# MotorCell_noPow.net
KiCad netlist of a schematic drawn in Altium Designer
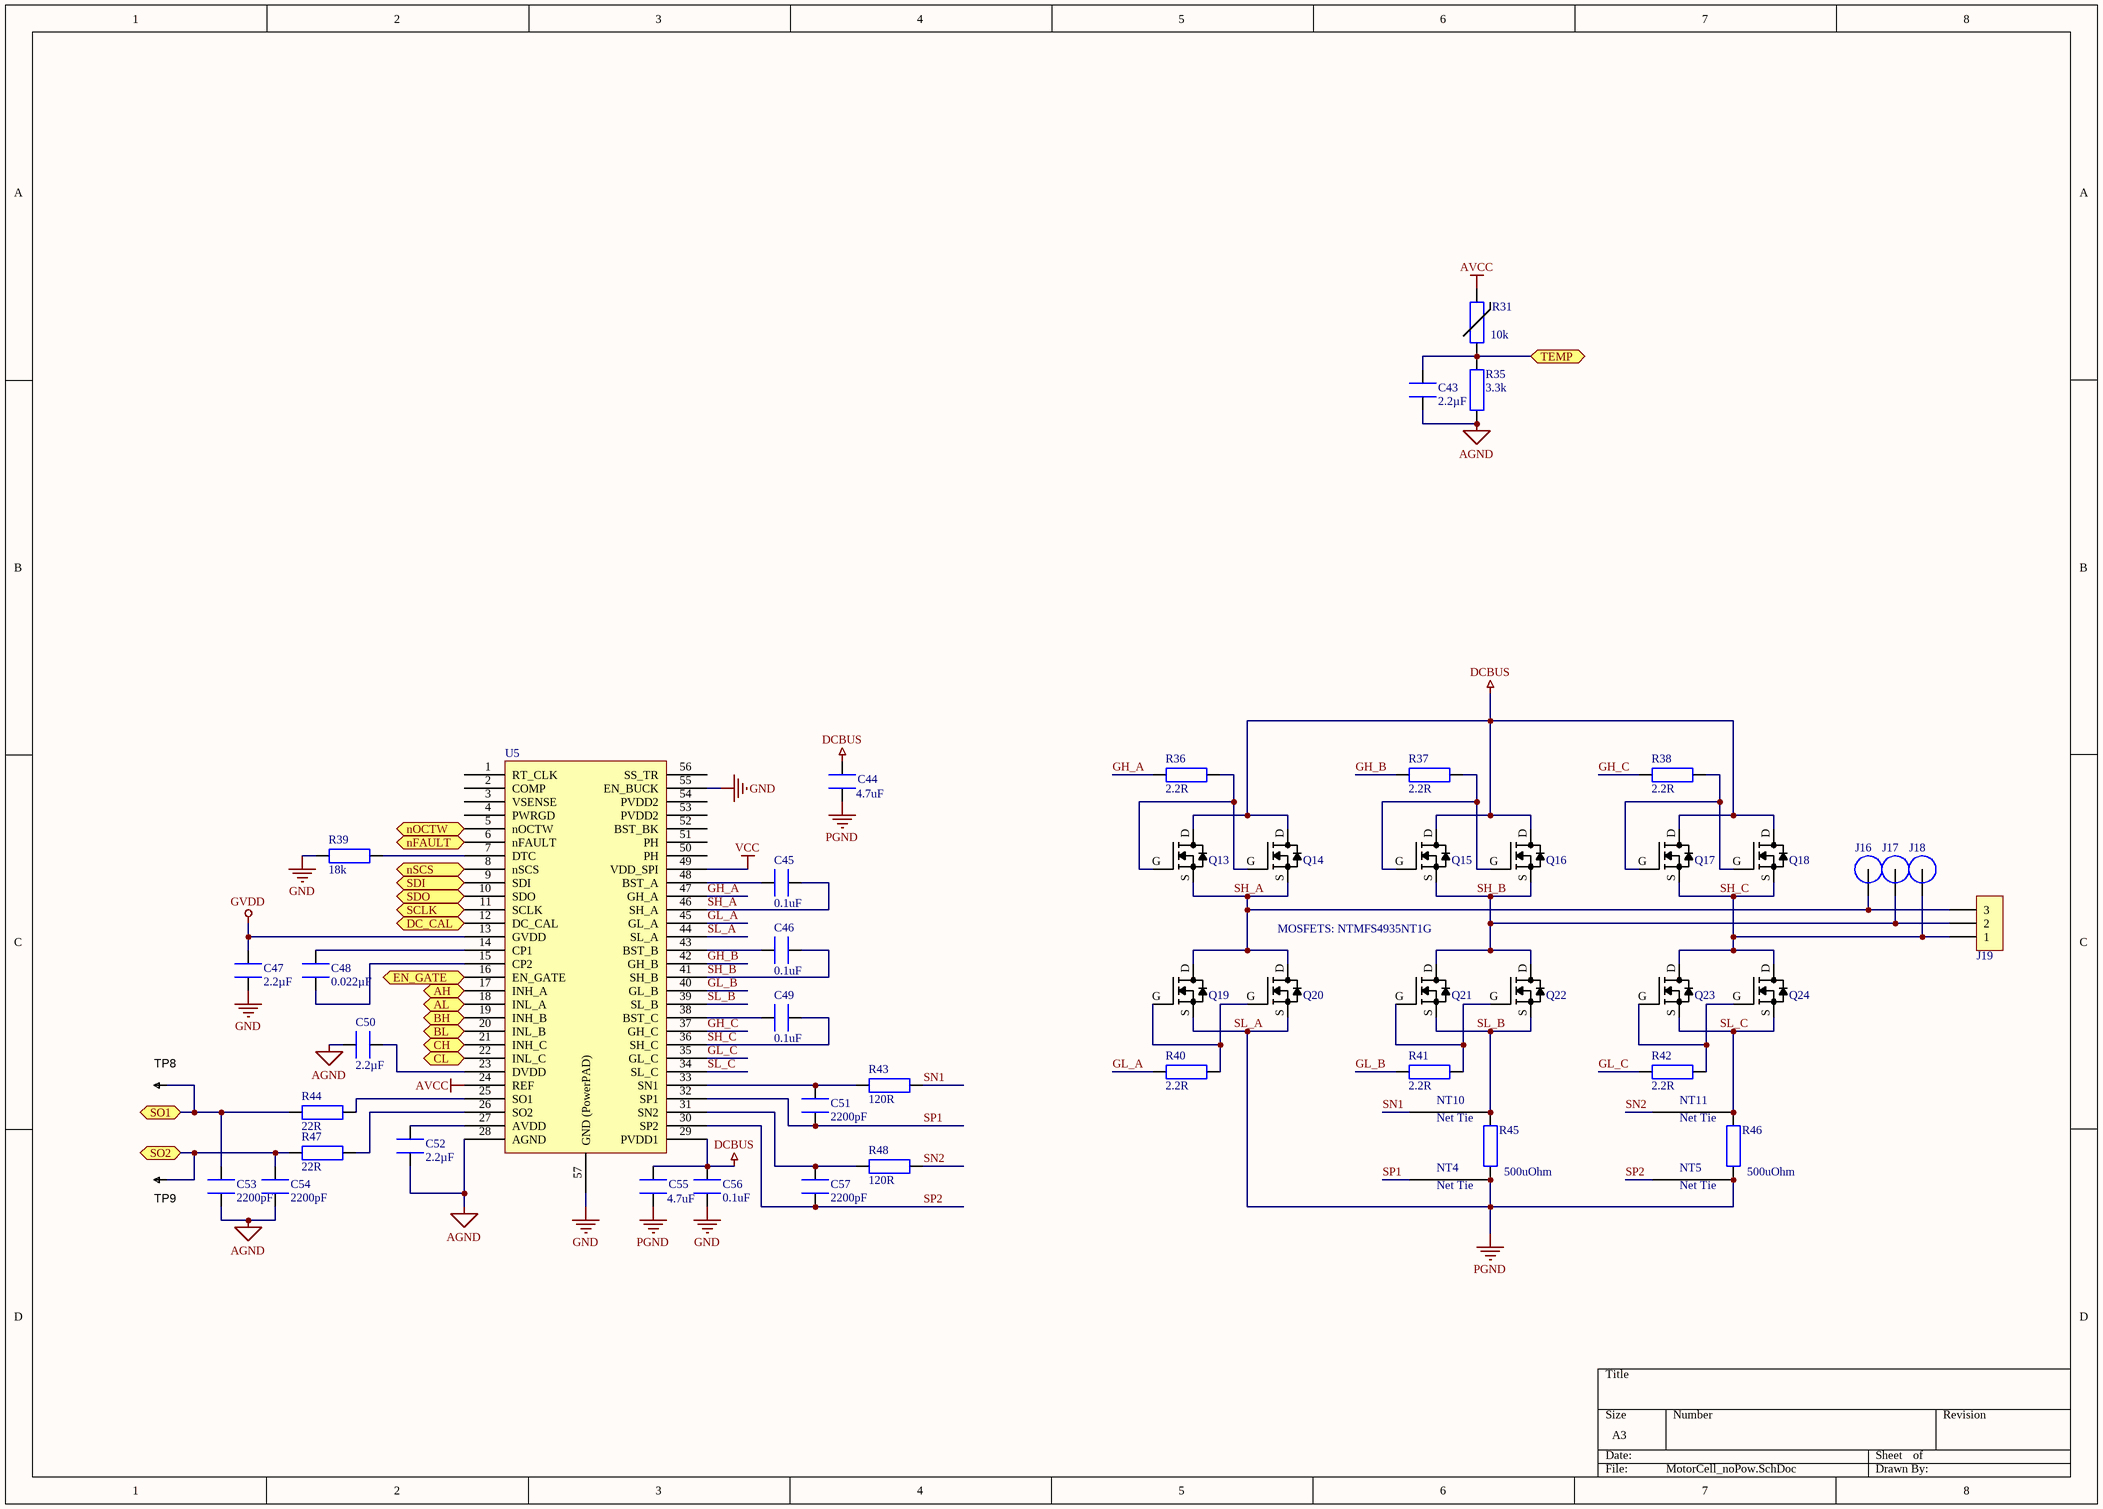
[diagram p0: MotorCell_noPow.SchDoc]

(export (version "E")
  (design (tool "Eeschema 10.0.6"))
  (components
    (comp (ref "C43")
      (value "2.2µF")
      (footprint "CAPC1608X09L")
      (description "CAP CER 2.2UF 16V X5R 0603")
      (fields
        (field (name "MANUFACTURER") "Murata Electronics North America")
        (field (name "MANUFACTURER PART NUMBER") "GRM188R61C225KE15D")
      )
      (libsource (lib "CustomComponents") (part "GRM188R61C225KE15D"))
    )
    (comp (ref "C44")
      (value "4.7uF")
      (footprint "CAPC2012X09N")
      (description "CAP CER 4.7UF 35V X5R 0805")
      (fields
        (field (name "MANUFACTURER") "Murata Electronics North America")
        (field (name "TOLERANCE") "±10%")
      )
      (libsource (lib "CustomComponents") (part "GRM219R6YA475KA73D"))
    )
    (comp (ref "C45")
      (value "0.1uF")
      (footprint "CAPC1608X09L")
      (description "CAP CER 0.1UF 50V X7R 0603")
      (fields
        (field (name "MANUFACTURER") "Murata Electronics North America")
        (field (name "MANUFACTURER PART NUMBER") "GRM188R71H104KA93D")
      )
      (libsource (lib "CustomComponents") (part "GRM188R71H104KA93D"))
    )
    (comp (ref "C46")
      (value "0.1uF")
      (footprint "CAPC1608X09L")
      (description "CAP CER 0.1UF 50V X7R 0603")
      (fields
        (field (name "MANUFACTURER") "Murata Electronics North America")
        (field (name "MANUFACTURER PART NUMBER") "GRM188R71H104KA93D")
      )
      (libsource (lib "CustomComponents") (part "GRM188R71H104KA93D"))
    )
    (comp (ref "C47")
      (value "2.2µF")
      (footprint "CAPC1608X09L")
      (description "CAP CER 2.2UF 16V X5R 0603")
      (fields
        (field (name "MANUFACTURER") "Murata Electronics North America")
        (field (name "MANUFACTURER PART NUMBER") "GRM188R61C225KE15D")
      )
      (libsource (lib "CustomComponents") (part "GRM188R61C225KE15D"))
    )
    (comp (ref "C48")
      (value "0.022µF")
      (footprint "CAPC1608X09L")
      (description "CAP CER 0.022UF 50V X7R 0603")
      (fields
        (field (name "MANUFACTURER") "Murata Electronics North America")
        (field (name "MANUFACTURER PART NUMBER") "GRM188R71H223KA01D")
      )
      (libsource (lib "CustomComponents") (part "GRM188R71H223KA01D"))
    )
    (comp (ref "C49")
      (value "0.1uF")
      (footprint "CAPC1608X09L")
      (description "CAP CER 0.1UF 50V X7R 0603")
      (fields
        (field (name "MANUFACTURER") "Murata Electronics North America")
        (field (name "MANUFACTURER PART NUMBER") "GRM188R71H104KA93D")
      )
      (libsource (lib "CustomComponents") (part "GRM188R71H104KA93D"))
    )
    (comp (ref "C50")
      (value "2.2µF")
      (footprint "CAPC1608X09L")
      (description "CAP CER 2.2UF 16V X5R 0603")
      (fields
        (field (name "MANUFACTURER") "Murata Electronics North America")
        (field (name "MANUFACTURER PART NUMBER") "GRM188R61C225KE15D")
      )
      (libsource (lib "CustomComponents") (part "GRM188R61C225KE15D"))
    )
    (comp (ref "C51")
      (value "2200pF")
      (footprint "CAPC1608X09L")
      (description "CAP CER 2200PF 50V NP0 0603")
      (fields
        (field (name "MANUFACTURER") "Murata Electronics North America")
        (field (name "TOLERANCE") "±5%")
      )
      (libsource (lib "CustomComponents") (part "GRM1885C1H222JA01D"))
    )
    (comp (ref "C52")
      (value "2.2µF")
      (footprint "CAPC1608X09L")
      (description "CAP CER 2.2UF 16V X5R 0603")
      (fields
        (field (name "MANUFACTURER") "Murata Electronics North America")
        (field (name "MANUFACTURER PART NUMBER") "GRM188R61C225KE15D")
      )
      (libsource (lib "CustomComponents") (part "GRM188R61C225KE15D"))
    )
    (comp (ref "C53")
      (value "2200pF")
      (footprint "CAPC1608X09L")
      (description "CAP CER 2200PF 50V NP0 0603")
      (fields
        (field (name "MANUFACTURER") "Murata Electronics North America")
        (field (name "TOLERANCE") "±5%")
      )
      (libsource (lib "CustomComponents") (part "GRM1885C1H222JA01D"))
    )
    (comp (ref "C54")
      (value "2200pF")
      (footprint "CAPC1608X09L")
      (description "CAP CER 2200PF 50V NP0 0603")
      (fields
        (field (name "MANUFACTURER") "Murata Electronics North America")
        (field (name "TOLERANCE") "±5%")
      )
      (libsource (lib "CustomComponents") (part "GRM1885C1H222JA01D"))
    )
    (comp (ref "C55")
      (value "4.7uF")
      (footprint "CAPC2012X09N")
      (description "CAP CER 4.7UF 35V X5R 0805")
      (fields
        (field (name "MANUFACTURER") "Murata Electronics North America")
        (field (name "TOLERANCE") "±10%")
      )
      (libsource (lib "CustomComponents") (part "GRM219R6YA475KA73D"))
    )
    (comp (ref "C56")
      (value "0.1uF")
      (footprint "CAPC1608X09L")
      (description "CAP CER 0.1UF 50V X7R 0603")
      (fields
        (field (name "MANUFACTURER") "Murata Electronics North America")
        (field (name "MANUFACTURER PART NUMBER") "GRM188R71H104KA93D")
      )
      (libsource (lib "CustomComponents") (part "GRM188R71H104KA93D"))
    )
    (comp (ref "C57")
      (value "2200pF")
      (footprint "CAPC1608X09L")
      (description "CAP CER 2200PF 50V NP0 0603")
      (fields
        (field (name "MANUFACTURER") "Murata Electronics North America")
        (field (name "TOLERANCE") "±5%")
      )
      (libsource (lib "CustomComponents") (part "GRM1885C1H222JA01D"))
    )
    (comp (ref "J16")
      (value "~")
      (footprint "M3 Spade Hole")
      (description "M3 Spade Terminal")
      (libsource (lib "CustomComponents") (part "M3 Spade Terminal"))
    )
    (comp (ref "J17")
      (value "~")
      (footprint "M3 Spade Hole")
      (description "M3 Spade Terminal")
      (libsource (lib "CustomComponents") (part "M3 Spade Terminal"))
    )
    (comp (ref "J18")
      (value "~")
      (footprint "M3 Spade Hole")
      (description "M3 Spade Terminal")
      (libsource (lib "CustomComponents") (part "M3 Spade Terminal"))
    )
    (comp (ref "J19")
      (value "1704936")
      (footprint "1704936")
      (description "CONN TERM BLOCK 3POS 7.62MM")
      (fields (field (name "MANUFACTURER") "Phoenix Contact") (field (name "VOLTAGE") "300V"))
      (libsource (lib "CustomComponents") (part "1704936"))
    )
    (comp (ref "NT4")
      (value "0.25mm")
      (footprint "NetTie_0.25mm")
      (libsource (lib "CustomComponents") (part "NetTie_0.25mm"))
    )
    (comp (ref "NT5")
      (value "0.25mm")
      (footprint "NetTie_0.25mm")
      (libsource (lib "CustomComponents") (part "NetTie_0.25mm"))
    )
    (comp (ref "NT10")
      (value "0.25mm")
      (footprint "NetTie_0.25mm")
      (libsource (lib "CustomComponents") (part "NetTie_0.25mm"))
    )
    (comp (ref "NT11")
      (value "0.25mm")
      (footprint "NetTie_0.25mm")
      (libsource (lib "CustomComponents") (part "NetTie_0.25mm"))
    )
    (comp (ref "Q13")
      (value "~")
      (footprint "SO8FL")
      (description "MOSFET N-CH 30V 13A SO8FL")
      (fields
        (field (name "MANUFACTURER") "ON Semiconductor")
        (field (name "MANUFACTURER PART NUMBER") "NTMFS4935NT1G")
      )
      (libsource (lib "CustomComponents") (part "NTMFS4935NT1G"))
    )
    (comp (ref "Q14")
      (value "FILL_FOOTPRINT")
      (footprint "SO8FL_FILL")
      (description "MOSFET N-CH 30V 13A SO8FL")
      (fields
        (field (name "MANUFACTURER") "ON Semiconductor")
        (field (name "MANUFACTURER PART NUMBER") "NTMFS4935NT1G")
      )
      (libsource (lib "CustomComponents") (part "NTMFS4935NT1G"))
    )
    (comp (ref "Q15")
      (value "~")
      (footprint "SO8FL")
      (description "MOSFET N-CH 30V 13A SO8FL")
      (fields
        (field (name "MANUFACTURER") "ON Semiconductor")
        (field (name "MANUFACTURER PART NUMBER") "NTMFS4935NT1G")
      )
      (libsource (lib "CustomComponents") (part "NTMFS4935NT1G"))
    )
    (comp (ref "Q16")
      (value "FILL_FOOTPRINT")
      (footprint "SO8FL_FILL")
      (description "MOSFET N-CH 30V 13A SO8FL")
      (fields
        (field (name "MANUFACTURER") "ON Semiconductor")
        (field (name "MANUFACTURER PART NUMBER") "NTMFS4935NT1G")
      )
      (libsource (lib "CustomComponents") (part "NTMFS4935NT1G"))
    )
    (comp (ref "Q17")
      (value "~")
      (footprint "SO8FL")
      (description "MOSFET N-CH 30V 13A SO8FL")
      (fields
        (field (name "MANUFACTURER") "ON Semiconductor")
        (field (name "MANUFACTURER PART NUMBER") "NTMFS4935NT1G")
      )
      (libsource (lib "CustomComponents") (part "NTMFS4935NT1G"))
    )
    (comp (ref "Q18")
      (value "FILL_FOOTPRINT")
      (footprint "SO8FL_FILL")
      (description "MOSFET N-CH 30V 13A SO8FL")
      (fields
        (field (name "MANUFACTURER") "ON Semiconductor")
        (field (name "MANUFACTURER PART NUMBER") "NTMFS4935NT1G")
      )
      (libsource (lib "CustomComponents") (part "NTMFS4935NT1G"))
    )
    (comp (ref "Q19")
      (value "~")
      (footprint "SO8FL")
      (description "MOSFET N-CH 30V 13A SO8FL")
      (fields
        (field (name "MANUFACTURER") "ON Semiconductor")
        (field (name "MANUFACTURER PART NUMBER") "NTMFS4935NT1G")
      )
      (libsource (lib "CustomComponents") (part "NTMFS4935NT1G"))
    )
    (comp (ref "Q20")
      (value "~")
      (footprint "SO8FL")
      (description "MOSFET N-CH 30V 13A SO8FL")
      (fields
        (field (name "MANUFACTURER") "ON Semiconductor")
        (field (name "MANUFACTURER PART NUMBER") "NTMFS4935NT1G")
      )
      (libsource (lib "CustomComponents") (part "NTMFS4935NT1G"))
    )
    (comp (ref "Q21")
      (value "~")
      (footprint "SO8FL")
      (description "MOSFET N-CH 30V 13A SO8FL")
      (fields
        (field (name "MANUFACTURER") "ON Semiconductor")
        (field (name "MANUFACTURER PART NUMBER") "NTMFS4935NT1G")
      )
      (libsource (lib "CustomComponents") (part "NTMFS4935NT1G"))
    )
    (comp (ref "Q22")
      (value "~")
      (footprint "SO8FL")
      (description "MOSFET N-CH 30V 13A SO8FL")
      (fields
        (field (name "MANUFACTURER") "ON Semiconductor")
        (field (name "MANUFACTURER PART NUMBER") "NTMFS4935NT1G")
      )
      (libsource (lib "CustomComponents") (part "NTMFS4935NT1G"))
    )
    (comp (ref "Q23")
      (value "~")
      (footprint "SO8FL")
      (description "MOSFET N-CH 30V 13A SO8FL")
      (fields
        (field (name "MANUFACTURER") "ON Semiconductor")
        (field (name "MANUFACTURER PART NUMBER") "NTMFS4935NT1G")
      )
      (libsource (lib "CustomComponents") (part "NTMFS4935NT1G"))
    )
    (comp (ref "Q24")
      (value "~")
      (footprint "SO8FL")
      (description "MOSFET N-CH 30V 13A SO8FL")
      (fields
        (field (name "MANUFACTURER") "ON Semiconductor")
        (field (name "MANUFACTURER PART NUMBER") "NTMFS4935NT1G")
      )
      (libsource (lib "CustomComponents") (part "NTMFS4935NT1G"))
    )
    (comp (ref "R31")
      (value "10k")
      (footprint "RESC1005X40N")
      (description "THERMISTOR 10K OHM NTC 0402 SMD")
      (libsource (lib "CustomComponents") (part "NCP15XH103F03RC"))
    )
    (comp (ref "R35")
      (value "3.3k")
      (footprint "RESC1608X55N")
      (description "RES SMD 3.3K OHM 1% 1/10W 0603")
      (fields
        (field (name "MANUFACTURER") "Yageo")
        (field (name "MANUFACTURER PART NUMBER") "RC0603FR-073K3L")
      )
      (libsource (lib "CustomComponents") (part "RC0603FR-073K3L"))
    )
    (comp (ref "R36")
      (value "2.2R")
      (footprint "RESC1608X55N")
      (description "RES SMD 2.2 OHM 1% 1/10W 0603")
      (fields
        (field (name "MANUFACTURER") "Yageo")
        (field (name "MANUFACTURER PART NUMBER") "RC0603FR-072R2L")
      )
      (libsource (lib "CustomComponents") (part "RC0603FR-072R2L"))
    )
    (comp (ref "R37")
      (value "2.2R")
      (footprint "RESC1608X55N")
      (description "RES SMD 2.2 OHM 1% 1/10W 0603")
      (fields
        (field (name "MANUFACTURER") "Yageo")
        (field (name "MANUFACTURER PART NUMBER") "RC0603FR-072R2L")
      )
      (libsource (lib "CustomComponents") (part "RC0603FR-072R2L"))
    )
    (comp (ref "R38")
      (value "2.2R")
      (footprint "RESC1608X55N")
      (description "RES SMD 2.2 OHM 1% 1/10W 0603")
      (fields
        (field (name "MANUFACTURER") "Yageo")
        (field (name "MANUFACTURER PART NUMBER") "RC0603FR-072R2L")
      )
      (libsource (lib "CustomComponents") (part "RC0603FR-072R2L"))
    )
    (comp (ref "R39")
      (value "18k")
      (footprint "RESC1608X55N")
      (description "RES SMD 18K OHM 1% 1/10W 0603")
      (fields
        (field (name "MANUFACTURER") "Yageo")
        (field (name "MANUFACTURER PART NUMBER") "RC0603FR-0718KL")
      )
      (libsource (lib "CustomComponents") (part "RC0603FR-0718KL"))
    )
    (comp (ref "R40")
      (value "2.2R")
      (footprint "RESC1608X55N")
      (description "RES SMD 2.2 OHM 1% 1/10W 0603")
      (fields
        (field (name "MANUFACTURER") "Yageo")
        (field (name "MANUFACTURER PART NUMBER") "RC0603FR-072R2L")
      )
      (libsource (lib "CustomComponents") (part "RC0603FR-072R2L"))
    )
    (comp (ref "R41")
      (value "2.2R")
      (footprint "RESC1608X55N")
      (description "RES SMD 2.2 OHM 1% 1/10W 0603")
      (fields
        (field (name "MANUFACTURER") "Yageo")
        (field (name "MANUFACTURER PART NUMBER") "RC0603FR-072R2L")
      )
      (libsource (lib "CustomComponents") (part "RC0603FR-072R2L"))
    )
    (comp (ref "R42")
      (value "2.2R")
      (footprint "RESC1608X55N")
      (description "RES SMD 2.2 OHM 1% 1/10W 0603")
      (fields
        (field (name "MANUFACTURER") "Yageo")
        (field (name "MANUFACTURER PART NUMBER") "RC0603FR-072R2L")
      )
      (libsource (lib "CustomComponents") (part "RC0603FR-072R2L"))
    )
    (comp (ref "R43")
      (value "120R")
      (footprint "RESC1608X55N")
      (description "RES SMD 120 OHM 1% 1/10W 0603")
      (fields
        (field (name "MANUFACTURER") "Yageo")
        (field (name "MANUFACTURER PART NUMBER") "RC0603FR-07120RL")
      )
      (libsource (lib "CustomComponents") (part "RC0603FR-07120RL"))
    )
    (comp (ref "R44")
      (value "22R")
      (footprint "RESC1608X55N")
      (description "RES SMD 22 OHM 1% 1/10W 0603")
      (fields
        (field (name "MANUFACTURER") "Yageo")
        (field (name "MANUFACTURER PART NUMBER") "RC0603FR-0722RL")
      )
      (libsource (lib "CustomComponents") (part "RC0603FR-0722RL"))
    )
    (comp (ref "R45")
      (value "500uOhm")
      (footprint "RESC6432X09N")
      (description "RES SMD 0.0005 OHM 1% 3W 2512")
      (fields (field (name "MANUFACTURER") "Riedon") (field (name "TOLERANCE") "±1%"))
      (libsource (lib "CustomComponents") (part "CSR2512C0R0005F"))
    )
    (comp (ref "R46")
      (value "500uOhm")
      (footprint "RESC6432X09N")
      (description "RES SMD 0.0005 OHM 1% 3W 2512")
      (fields (field (name "MANUFACTURER") "Riedon") (field (name "TOLERANCE") "±1%"))
      (libsource (lib "CustomComponents") (part "CSR2512C0R0005F"))
    )
    (comp (ref "R47")
      (value "22R")
      (footprint "RESC1608X55N")
      (description "RES SMD 22 OHM 1% 1/10W 0603")
      (fields
        (field (name "MANUFACTURER") "Yageo")
        (field (name "MANUFACTURER PART NUMBER") "RC0603FR-0722RL")
      )
      (libsource (lib "CustomComponents") (part "RC0603FR-0722RL"))
    )
    (comp (ref "R48")
      (value "120R")
      (footprint "RESC1608X55N")
      (description "RES SMD 120 OHM 1% 1/10W 0603")
      (fields
        (field (name "MANUFACTURER") "Yageo")
        (field (name "MANUFACTURER PART NUMBER") "RC0603FR-07120RL")
      )
      (libsource (lib "CustomComponents") (part "RC0603FR-07120RL"))
    )
    (comp (ref "TP8")
      (value "TESTPOINT")
      (footprint "TP-R30")
      (description "SMD test pin")
      (libsource (lib "PBL - Test Points") (part "TESTPOINT"))
    )
    (comp (ref "TP9")
      (value "TESTPOINT")
      (footprint "TP-R30")
      (description "SMD test pin")
      (libsource (lib "PBL - Test Points") (part "TESTPOINT"))
    )
    (comp (ref "U5")
      (value "~")
      (footprint "TSSOP50P810X120_HS-57N")
      (description "MOTOR DRIVER, 3PH, 56HTSSOP")
      (libsource (lib "CustomComponents") (part "DRV8301"))
    )
  )
  (nets
    (net (code "1") (name "/AH") (class "Default")
      (node (ref "U5") (pin "17") (pinfunction "INH_A_17") (pintype "passive"))
    )
    (net (code "2") (name "/AL") (class "Default")
      (node (ref "U5") (pin "18") (pinfunction "INL_A_18") (pintype "passive"))
    )
    (net (code "3") (name "/BH") (class "Default")
      (node (ref "U5") (pin "19") (pinfunction "INH_B_19") (pintype "passive"))
    )
    (net (code "4") (name "/BL") (class "Default")
      (node (ref "U5") (pin "20") (pinfunction "INL_B_20") (pintype "passive"))
    )
    (net (code "5") (name "/CH") (class "Default")
      (node (ref "U5") (pin "21") (pinfunction "INH_C_21") (pintype "passive"))
    )
    (net (code "6") (name "/CL") (class "Default")
      (node (ref "U5") (pin "22") (pinfunction "INL_C_22") (pintype "passive"))
    )
    (net (code "7") (name "/DC_CAL") (class "Default")
      (node (ref "U5") (pin "12") (pinfunction "DC_CAL_12") (pintype "passive"))
    )
    (net (code "8") (name "/EN_GATE") (class "Default")
      (node (ref "U5") (pin "16") (pinfunction "EN_GATE_16") (pintype "passive"))
    )
    (net (code "9") (name "/GH_A") (class "Default")
      (node (ref "R36") (pin "1") (pinfunction "0_1") (pintype "passive"))
      (node (ref "U5") (pin "47") (pinfunction "GH_A_47") (pintype "passive"))
    )
    (net (code "10") (name "/GH_B") (class "Default")
      (node (ref "R37") (pin "1") (pinfunction "0_1") (pintype "passive"))
      (node (ref "U5") (pin "42") (pinfunction "GH_B_42") (pintype "passive"))
    )
    (net (code "11") (name "/GH_C") (class "Default")
      (node (ref "R38") (pin "1") (pinfunction "0_1") (pintype "passive"))
      (node (ref "U5") (pin "37") (pinfunction "GH_C_37") (pintype "passive"))
    )
    (net (code "12") (name "/GL_A") (class "Default")
      (node (ref "R40") (pin "1") (pinfunction "0_1") (pintype "passive"))
      (node (ref "U5") (pin "45") (pinfunction "GL_A_45") (pintype "passive"))
    )
    (net (code "13") (name "/GL_B") (class "Default")
      (node (ref "R41") (pin "1") (pinfunction "0_1") (pintype "passive"))
      (node (ref "U5") (pin "40") (pinfunction "GL_B_40") (pintype "passive"))
    )
    (net (code "14") (name "/GL_C") (class "Default")
      (node (ref "R42") (pin "1") (pinfunction "0_1") (pintype "passive"))
      (node (ref "U5") (pin "35") (pinfunction "GL_C_35") (pintype "passive"))
    )
    (net (code "15") (name "/SCLK") (class "Default")
      (node (ref "U5") (pin "11") (pinfunction "SCLK_11") (pintype "passive"))
    )
    (net (code "16") (name "/SDI") (class "Default")
      (node (ref "U5") (pin "9") (pinfunction "SDI_9") (pintype "passive"))
    )
    (net (code "17") (name "/SDO") (class "Default")
      (node (ref "U5") (pin "10") (pinfunction "SDO_10") (pintype "passive"))
    )
    (net (code "18") (name "/SH_A") (class "Default")
      (node (ref "C45") (pin "1") (pinfunction "1_1") (pintype "passive"))
      (node (ref "J16") (pin "1") (pinfunction "1_1") (pintype "passive"))
      (node (ref "J19") (pin "3") (pinfunction "3_3") (pintype "passive"))
      (node (ref "Q13") (pin "S") (pinfunction "S_S") (pintype "passive"))
      (node (ref "Q14") (pin "S") (pinfunction "S_S") (pintype "passive"))
      (node (ref "Q19") (pin "D") (pinfunction "D_D") (pintype "passive"))
      (node (ref "Q20") (pin "D") (pinfunction "D_D") (pintype "passive"))
      (node (ref "U5") (pin "46") (pinfunction "SH_A_46") (pintype "passive"))
    )
    (net (code "19") (name "/SH_B") (class "Default")
      (node (ref "C46") (pin "1") (pinfunction "1_1") (pintype "passive"))
      (node (ref "J17") (pin "1") (pinfunction "1_1") (pintype "passive"))
      (node (ref "J19") (pin "2") (pinfunction "2_2") (pintype "passive"))
      (node (ref "Q15") (pin "S") (pinfunction "S_S") (pintype "passive"))
      (node (ref "Q16") (pin "S") (pinfunction "S_S") (pintype "passive"))
      (node (ref "Q21") (pin "D") (pinfunction "D_D") (pintype "passive"))
      (node (ref "Q22") (pin "D") (pinfunction "D_D") (pintype "passive"))
      (node (ref "U5") (pin "41") (pinfunction "SH_B_41") (pintype "passive"))
    )
    (net (code "20") (name "/SH_C") (class "Default")
      (node (ref "C49") (pin "1") (pinfunction "1_1") (pintype "passive"))
      (node (ref "J18") (pin "1") (pinfunction "1_1") (pintype "passive"))
      (node (ref "J19") (pin "1") (pinfunction "1_1") (pintype "passive"))
      (node (ref "Q17") (pin "S") (pinfunction "S_S") (pintype "passive"))
      (node (ref "Q18") (pin "S") (pinfunction "S_S") (pintype "passive"))
      (node (ref "Q23") (pin "D") (pinfunction "D_D") (pintype "passive"))
      (node (ref "Q24") (pin "D") (pinfunction "D_D") (pintype "passive"))
      (node (ref "U5") (pin "36") (pinfunction "SH_C_36") (pintype "passive"))
    )
    (net (code "21") (name "/SL_B") (class "Default")
      (node (ref "NT10") (pin "2") (pintype "passive"))
      (node (ref "Q21") (pin "S") (pinfunction "S_S") (pintype "passive"))
      (node (ref "Q22") (pin "S") (pinfunction "S_S") (pintype "passive"))
      (node (ref "R45") (pin "2") (pinfunction "0_2") (pintype "passive"))
      (node (ref "U5") (pin "39") (pinfunction "SL_B_39") (pintype "passive"))
    )
    (net (code "22") (name "/SL_C") (class "Default")
      (node (ref "NT11") (pin "2") (pintype "passive"))
      (node (ref "Q23") (pin "S") (pinfunction "S_S") (pintype "passive"))
      (node (ref "Q24") (pin "S") (pinfunction "S_S") (pintype "passive"))
      (node (ref "R46") (pin "2") (pinfunction "0_2") (pintype "passive"))
      (node (ref "U5") (pin "34") (pinfunction "SL_C_34") (pintype "passive"))
    )
    (net (code "23") (name "/SN1") (class "Default")
      (node (ref "NT10") (pin "1") (pintype "passive"))
      (node (ref "R43") (pin "1") (pinfunction "0_1") (pintype "passive"))
    )
    (net (code "24") (name "/SN2") (class "Default")
      (node (ref "NT11") (pin "1") (pintype "passive"))
      (node (ref "R48") (pin "1") (pinfunction "0_1") (pintype "passive"))
    )
    (net (code "25") (name "/SO1") (class "Default")
      (node (ref "C53") (pin "1") (pinfunction "1_1") (pintype "passive"))
      (node (ref "R44") (pin "2") (pinfunction "0_2") (pintype "passive"))
      (node (ref "TP8") (pin "1") (pintype "passive"))
    )
    (net (code "26") (name "/SO2") (class "Default")
      (node (ref "C54") (pin "1") (pinfunction "1_1") (pintype "passive"))
      (node (ref "R47") (pin "2") (pinfunction "0_2") (pintype "passive"))
      (node (ref "TP9") (pin "1") (pintype "passive"))
    )
    (net (code "27") (name "/SP1") (class "Default")
      (node (ref "C51") (pin "2") (pinfunction "2_2") (pintype "passive"))
      (node (ref "NT4") (pin "1") (pintype "passive"))
      (node (ref "U5") (pin "32") (pinfunction "SP1_32") (pintype "passive"))
    )
    (net (code "28") (name "/SP2") (class "Default")
      (node (ref "C57") (pin "2") (pinfunction "2_2") (pintype "passive"))
      (node (ref "NT5") (pin "1") (pintype "passive"))
      (node (ref "U5") (pin "30") (pinfunction "SP2_30") (pintype "passive"))
    )
    (net (code "29") (name "/TEMP") (class "Default")
      (node (ref "C43") (pin "2") (pinfunction "2_2") (pintype "passive"))
      (node (ref "R31") (pin "1") (pinfunction "0_1") (pintype "passive"))
      (node (ref "R35") (pin "1") (pinfunction "0_1") (pintype "passive"))
    )
    (net (code "30") (name "/nFAULT") (class "Default")
      (node (ref "U5") (pin "6") (pinfunction "nFAULT_6") (pintype "passive"))
    )
    (net (code "31") (name "/nOCTW") (class "Default")
      (node (ref "U5") (pin "5") (pinfunction "nOCTW_5") (pintype "passive"))
    )
    (net (code "32") (name "/nSCS") (class "Default")
      (node (ref "U5") (pin "8") (pinfunction "nSCS_8") (pintype "passive"))
    )
    (net (code "33") (name "AGND") (class "Default")
      (node (ref "C43") (pin "1") (pinfunction "1_1") (pintype "passive"))
      (node (ref "C50") (pin "1") (pinfunction "1_1") (pintype "passive"))
      (node (ref "C52") (pin "1") (pinfunction "1_1") (pintype "passive"))
      (node (ref "C53") (pin "2") (pinfunction "2_2") (pintype "passive"))
      (node (ref "C54") (pin "2") (pinfunction "2_2") (pintype "passive"))
      (node (ref "R35") (pin "2") (pinfunction "0_2") (pintype "passive"))
      (node (ref "U5") (pin "28") (pinfunction "AGND_28") (pintype "passive"))
    )
    (net (code "34") (name "AVCC") (class "Default")
      (node (ref "R31") (pin "2") (pinfunction "0_2") (pintype "passive"))
      (node (ref "U5") (pin "24") (pinfunction "REF_24") (pintype "passive"))
    )
    (net (code "35") (name "DCBUS") (class "Default")
      (node (ref "C44") (pin "2") (pinfunction "2_2") (pintype "passive"))
      (node (ref "C55") (pin "2") (pinfunction "2_2") (pintype "passive"))
      (node (ref "C56") (pin "1") (pinfunction "1_1") (pintype "passive"))
      (node (ref "Q13") (pin "D") (pinfunction "D_D") (pintype "passive"))
      (node (ref "Q14") (pin "D") (pinfunction "D_D") (pintype "passive"))
      (node (ref "Q15") (pin "D") (pinfunction "D_D") (pintype "passive"))
      (node (ref "Q16") (pin "D") (pinfunction "D_D") (pintype "passive"))
      (node (ref "Q17") (pin "D") (pinfunction "D_D") (pintype "passive"))
      (node (ref "Q18") (pin "D") (pinfunction "D_D") (pintype "passive"))
      (node (ref "U5") (pin "29") (pinfunction "PVDD1_29") (pintype "passive"))
    )
    (net (code "36") (name "GND") (class "Default")
      (node (ref "C47") (pin "1") (pinfunction "1_1") (pintype "passive"))
      (node (ref "C56") (pin "2") (pinfunction "2_2") (pintype "passive"))
      (node (ref "R39") (pin "2") (pinfunction "0_2") (pintype "passive"))
      (node (ref "U5") (pin "55") (pinfunction "EN_BUCK_55") (pintype "passive"))
      (node (ref "U5") (pin "57") (pinfunction "GND_(PowerPAD)_57") (pintype "passive"))
    )
    (net (code "37") (name "GVDD") (class "Default")
      (node (ref "C47") (pin "2") (pinfunction "2_2") (pintype "passive"))
      (node (ref "U5") (pin "13") (pinfunction "GVDD_13") (pintype "passive"))
    )
    (net (code "38") (name "Net-(Q13-PadG)") (class "Default")
      (node (ref "Q13") (pin "G") (pinfunction "G_G") (pintype "passive"))
      (node (ref "Q14") (pin "G") (pinfunction "G_G") (pintype "passive"))
      (node (ref "R36") (pin "2") (pinfunction "0_2") (pintype "passive"))
    )
    (net (code "39") (name "Net-(Q15-PadG)") (class "Default")
      (node (ref "Q15") (pin "G") (pinfunction "G_G") (pintype "passive"))
      (node (ref "Q16") (pin "G") (pinfunction "G_G") (pintype "passive"))
      (node (ref "R37") (pin "2") (pinfunction "0_2") (pintype "passive"))
    )
    (net (code "40") (name "Net-(Q17-PadG)") (class "Default")
      (node (ref "Q17") (pin "G") (pinfunction "G_G") (pintype "passive"))
      (node (ref "Q18") (pin "G") (pinfunction "G_G") (pintype "passive"))
      (node (ref "R38") (pin "2") (pinfunction "0_2") (pintype "passive"))
    )
    (net (code "41") (name "Net-(Q19-PadG)") (class "Default")
      (node (ref "Q19") (pin "G") (pinfunction "G_G") (pintype "passive"))
      (node (ref "Q20") (pin "G") (pinfunction "G_G") (pintype "passive"))
      (node (ref "R40") (pin "2") (pinfunction "0_2") (pintype "passive"))
    )
    (net (code "42") (name "Net-(Q21-PadG)") (class "Default")
      (node (ref "Q21") (pin "G") (pinfunction "G_G") (pintype "passive"))
      (node (ref "Q22") (pin "G") (pinfunction "G_G") (pintype "passive"))
      (node (ref "R41") (pin "2") (pinfunction "0_2") (pintype "passive"))
    )
    (net (code "43") (name "Net-(Q23-PadG)") (class "Default")
      (node (ref "Q23") (pin "G") (pinfunction "G_G") (pintype "passive"))
      (node (ref "Q24") (pin "G") (pinfunction "G_G") (pintype "passive"))
      (node (ref "R42") (pin "2") (pinfunction "0_2") (pintype "passive"))
    )
    (net (code "44") (name "Net-(U5-AVDD)") (class "Default")
      (node (ref "C52") (pin "2") (pinfunction "2_2") (pintype "passive"))
      (node (ref "U5") (pin "27") (pinfunction "AVDD_27") (pintype "passive"))
    )
    (net (code "45") (name "Net-(U5-BST_A)") (class "Default")
      (node (ref "C45") (pin "2") (pinfunction "2_2") (pintype "passive"))
      (node (ref "U5") (pin "48") (pinfunction "BST_A_48") (pintype "passive"))
    )
    (net (code "46") (name "Net-(U5-BST_B)") (class "Default")
      (node (ref "C46") (pin "2") (pinfunction "2_2") (pintype "passive"))
      (node (ref "U5") (pin "43") (pinfunction "BST_B_43") (pintype "passive"))
    )
    (net (code "47") (name "Net-(U5-BST_C)") (class "Default")
      (node (ref "C49") (pin "2") (pinfunction "2_2") (pintype "passive"))
      (node (ref "U5") (pin "38") (pinfunction "BST_C_38") (pintype "passive"))
    )
    (net (code "48") (name "Net-(U5-CP1)") (class "Default")
      (node (ref "C48") (pin "1") (pinfunction "1_1") (pintype "passive"))
      (node (ref "U5") (pin "14") (pinfunction "CP1_14") (pintype "passive"))
    )
    (net (code "49") (name "Net-(U5-CP2)") (class "Default")
      (node (ref "C48") (pin "2") (pinfunction "2_2") (pintype "passive"))
      (node (ref "U5") (pin "15") (pinfunction "CP2_15") (pintype "passive"))
    )
    (net (code "50") (name "Net-(U5-DTC)") (class "Default")
      (node (ref "R39") (pin "1") (pinfunction "0_1") (pintype "passive"))
      (node (ref "U5") (pin "7") (pinfunction "DTC_7") (pintype "passive"))
    )
    (net (code "51") (name "Net-(U5-DVDD)") (class "Default")
      (node (ref "C50") (pin "2") (pinfunction "2_2") (pintype "passive"))
      (node (ref "U5") (pin "23") (pinfunction "DVDD_23") (pintype "passive"))
    )
    (net (code "52") (name "Net-(U5-SN1)") (class "Default")
      (node (ref "C51") (pin "1") (pinfunction "1_1") (pintype "passive"))
      (node (ref "R43") (pin "2") (pinfunction "0_2") (pintype "passive"))
      (node (ref "U5") (pin "33") (pinfunction "SN1_33") (pintype "passive"))
    )
    (net (code "53") (name "Net-(U5-SN2)") (class "Default")
      (node (ref "C57") (pin "1") (pinfunction "1_1") (pintype "passive"))
      (node (ref "R48") (pin "2") (pinfunction "0_2") (pintype "passive"))
      (node (ref "U5") (pin "31") (pinfunction "SN2_31") (pintype "passive"))
    )
    (net (code "54") (name "Net-(U5-SO1)") (class "Default")
      (node (ref "R44") (pin "1") (pinfunction "0_1") (pintype "passive"))
      (node (ref "U5") (pin "25") (pinfunction "SO1_25") (pintype "passive"))
    )
    (net (code "55") (name "Net-(U5-SO2)") (class "Default")
      (node (ref "R47") (pin "1") (pinfunction "0_1") (pintype "passive"))
      (node (ref "U5") (pin "26") (pinfunction "SO2_26") (pintype "passive"))
    )
    (net (code "56") (name "PGND") (class "Default")
      (node (ref "C44") (pin "1") (pinfunction "1_1") (pintype "passive"))
      (node (ref "C55") (pin "1") (pinfunction "1_1") (pintype "passive"))
      (node (ref "NT4") (pin "2") (pintype "passive"))
      (node (ref "NT5") (pin "2") (pintype "passive"))
      (node (ref "Q19") (pin "S") (pinfunction "S_S") (pintype "passive"))
      (node (ref "Q20") (pin "S") (pinfunction "S_S") (pintype "passive"))
      (node (ref "R45") (pin "1") (pinfunction "0_1") (pintype "passive"))
      (node (ref "R46") (pin "1") (pinfunction "0_1") (pintype "passive"))
      (node (ref "U5") (pin "44") (pinfunction "SL_A_44") (pintype "passive"))
    )
    (net (code "57") (name "VCC") (class "Default")
      (node (ref "U5") (pin "49") (pinfunction "VDD_SPI_49") (pintype "passive"))
    )
    (net (code "58") (name "unconnected-(U5-BST_BK-Pad52)") (class "Default")
      (node (ref "U5") (pin "52") (pinfunction "BST_BK_52") (pintype "passive"))
    )
    (net (code "59") (name "unconnected-(U5-COMP-Pad2)") (class "Default")
      (node (ref "U5") (pin "2") (pinfunction "COMP_2") (pintype "passive"))
    )
    (net (code "60") (name "unconnected-(U5-PH-Pad50)") (class "Default")
      (node (ref "U5") (pin "50") (pinfunction "PH_50") (pintype "passive"))
    )
    (net (code "61") (name "unconnected-(U5-PH-Pad51)") (class "Default")
      (node (ref "U5") (pin "51") (pinfunction "PH_51") (pintype "passive"))
    )
    (net (code "62") (name "unconnected-(U5-PVDD2-Pad53)") (class "Default")
      (node (ref "U5") (pin "53") (pinfunction "PVDD2_53") (pintype "passive"))
    )
    (net (code "63") (name "unconnected-(U5-PVDD2-Pad54)") (class "Default")
      (node (ref "U5") (pin "54") (pinfunction "PVDD2_54") (pintype "passive"))
    )
    (net (code "64") (name "unconnected-(U5-PWRGD-Pad4)") (class "Default")
      (node (ref "U5") (pin "4") (pinfunction "PWRGD_4") (pintype "passive"))
    )
    (net (code "65") (name "unconnected-(U5-RT_CLK-Pad1)") (class "Default")
      (node (ref "U5") (pin "1") (pinfunction "RT_CLK_1") (pintype "passive"))
    )
    (net (code "66") (name "unconnected-(U5-SS_TR-Pad56)") (class "Default")
      (node (ref "U5") (pin "56") (pinfunction "SS_TR_56") (pintype "passive"))
    )
    (net (code "67") (name "unconnected-(U5-VSENSE-Pad3)") (class "Default")
      (node (ref "U5") (pin "3") (pinfunction "VSENSE_3") (pintype "passive"))
    )
  )
)
